# MCP2515_PINOUT.net
KiCad netlist of a schematic drawn in Altium Designer
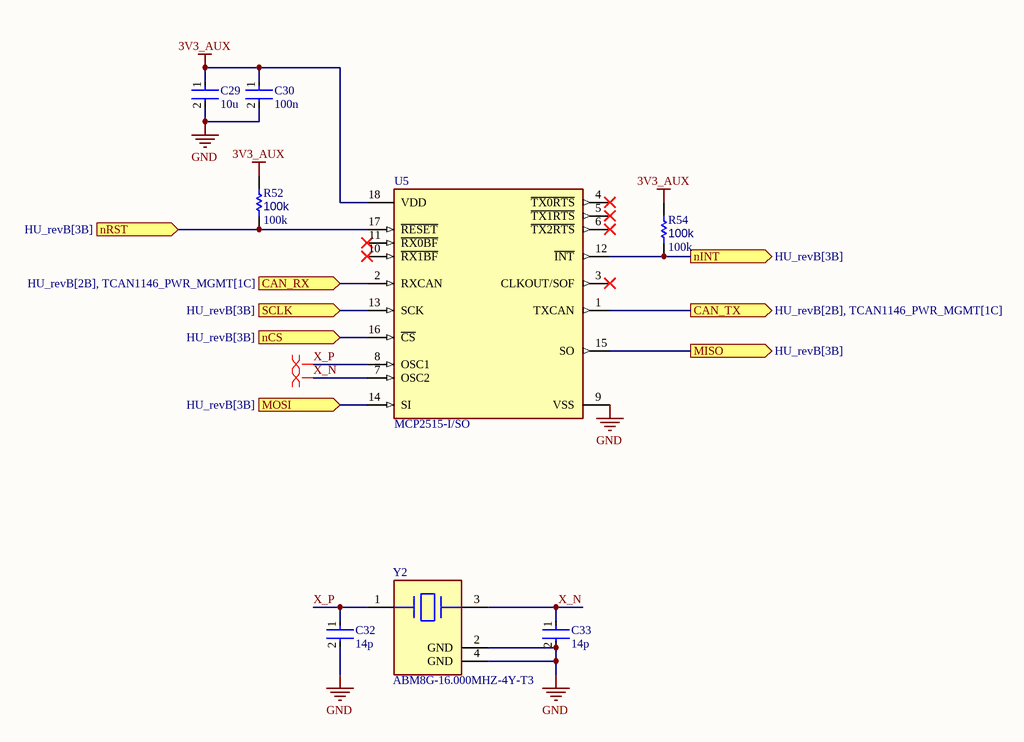
[diagram p0: MCP2515_PINOUT.SchDoc]

(export (version "E")
  (design (tool "Eeschema 10.0.6"))
  (components
    (comp (ref "C29")
      (value "10u")
      (footprint "FP-0402-L_1_0_0_05-W_0_5-IPC_A")
      (description "LARGE PADS, 0402 CAP, CHANGE COMMENT TO MATCH REAL P/N")
      (libsource (lib "Space Concordia") (part "b4654b650e69147ec39a6b967a45e02"))
    )
    (comp (ref "C30")
      (value "100n")
      (footprint "FP-0402-L_1_0_0_05-W_0_5-IPC_A")
      (description "LARGE PADS, 0402 CAP, CHANGE COMMENT TO MATCH REAL P/N")
      (libsource (lib "Space Concordia") (part "b4654b650e69147ec39a6b967a45e02"))
    )
    (comp (ref "C32")
      (value "14p")
      (footprint "FP-0402-L_1_0_0_05-W_0_5-IPC_A")
      (description "LARGE PADS, 0402 CAP, CHANGE COMMENT TO MATCH REAL P/N")
      (libsource (lib "Space Concordia") (part "b4654b650e69147ec39a6b967a45e02"))
    )
    (comp (ref "C33")
      (value "14p")
      (footprint "FP-0402-L_1_0_0_05-W_0_5-IPC_A")
      (description "LARGE PADS, 0402 CAP, CHANGE COMMENT TO MATCH REAL P/N")
      (libsource (lib "Space Concordia") (part "b4654b650e69147ec39a6b967a45e02"))
    )
    (comp (ref "R52")
      (value "100k")
      (footprint "R0603B")
      (description "Resistor")
      (fields (field (name "ALTIUM_VALUE") "100k"))
      (libsource (lib "Space Concordia") (part "Resistor"))
    )
    (comp (ref "R54")
      (value "100k")
      (footprint "R0603B")
      (description "Resistor")
      (fields (field (name "ALTIUM_VALUE") "100k"))
      (libsource (lib "Space Concordia") (part "Resistor"))
    )
    (comp (ref "U5")
      (value "MCP2515-I/SO")
      (footprint "FP-C04-051-MFG")
      (description "IC CAN CONTROLLER W/SPI 18SOIC")
      (fields
        (field (name "MANUFACTURER") "Microchip")
        (field (name "OCTOPART") "https://octopart.com/mcp2515-i%2Fso-microchip-430187")
      )
      (libsource (lib "Altium Content Vault") (part "1c78ea6ff576bac94664e2637e1b479"))
    )
    (comp (ref "Y2")
      (value "ABM8G-16.000MHZ-4Y-T3")
      (footprint "FP-ABM8G-MFG")
      (description "Crystal 16MHz ±30ppm (Tol) ±30ppm (Stability) 10pF FUND 80Ω 4-Pin SMD T/R")
      (libsource (lib "Altium Content Vault") (part "48e526d86b7f2615d98721063c72f49"))
    )
  )
  (nets
    (net (code "1") (name "/CAN_RX") (class "Default")
      (node (ref "U5") (pin "2") (pinfunction "RXCAN_2") (pintype "input"))
    )
    (net (code "2") (name "/CAN_TX") (class "Default")
      (node (ref "U5") (pin "1") (pinfunction "TXCAN_1") (pintype "output"))
    )
    (net (code "3") (name "/MISO") (class "Default")
      (node (ref "U5") (pin "15") (pinfunction "SO_15") (pintype "output"))
    )
    (net (code "4") (name "/MOSI") (class "Default")
      (node (ref "U5") (pin "14") (pinfunction "SI_14") (pintype "input"))
    )
    (net (code "5") (name "/SCLK") (class "Default")
      (node (ref "U5") (pin "13") (pinfunction "SCK_13") (pintype "input"))
    )
    (net (code "6") (name "/X_N") (class "Default")
      (node (ref "C33") (pin "1") (pinfunction "1_1") (pintype "passive"))
      (node (ref "U5") (pin "7") (pinfunction "OSC2_7") (pintype "input"))
      (node (ref "Y2") (pin "3") (pinfunction "3_3") (pintype "passive"))
    )
    (net (code "7") (name "/X_P") (class "Default")
      (node (ref "C32") (pin "1") (pinfunction "1_1") (pintype "passive"))
      (node (ref "U5") (pin "8") (pinfunction "OSC1_8") (pintype "input"))
      (node (ref "Y2") (pin "1") (pinfunction "1_1") (pintype "passive"))
    )
    (net (code "8") (name "/nCS") (class "Default")
      (node (ref "U5") (pin "16") (pinfunction "~{CS}_16") (pintype "input"))
    )
    (net (code "9") (name "/nINT") (class "Default")
      (node (ref "R54") (pin "2") (pinfunction "2_2") (pintype "passive"))
      (node (ref "U5") (pin "12") (pinfunction "~{INT}_12") (pintype "output"))
    )
    (net (code "10") (name "/nRST") (class "Default")
      (node (ref "R52") (pin "2") (pinfunction "2_2") (pintype "passive"))
      (node (ref "U5") (pin "17") (pinfunction "~{RESET}_17") (pintype "input"))
    )
    (net (code "11") (name "3V3_AUX") (class "Default")
      (node (ref "C29") (pin "1") (pinfunction "1_1") (pintype "passive"))
      (node (ref "C30") (pin "1") (pinfunction "1_1") (pintype "passive"))
      (node (ref "R52") (pin "1") (pinfunction "1_1") (pintype "passive"))
      (node (ref "R54") (pin "1") (pinfunction "1_1") (pintype "passive"))
      (node (ref "U5") (pin "18") (pinfunction "VDD_18") (pintype "power_in"))
    )
    (net (code "12") (name "GND") (class "Default")
      (node (ref "C29") (pin "2") (pinfunction "2_2") (pintype "passive"))
      (node (ref "C30") (pin "2") (pinfunction "2_2") (pintype "passive"))
      (node (ref "C32") (pin "2") (pinfunction "2_2") (pintype "passive"))
      (node (ref "C33") (pin "2") (pinfunction "2_2") (pintype "passive"))
      (node (ref "U5") (pin "9") (pinfunction "VSS_9") (pintype "power_in"))
      (node (ref "Y2") (pin "2") (pinfunction "GND_2") (pintype "power_in"))
      (node (ref "Y2") (pin "4") (pinfunction "GND_4") (pintype "power_in"))
    )
    (net (code "13") (name "unconnected-(U5-CLKOUT{slash}SOF-Pad3)") (class "Default")
      (node (ref "U5") (pin "3") (pinfunction "CLKOUT/SOF_3") (pintype "output+no_connect"))
    )
    (net (code "14") (name "unconnected-(U5-~{RX0BF}-Pad11)") (class "Default")
      (node (ref "U5") (pin "11") (pinfunction "~{RX0BF}_11") (pintype "input+no_connect"))
    )
    (net (code "15") (name "unconnected-(U5-~{RX1BF}-Pad10)") (class "Default")
      (node (ref "U5") (pin "10") (pinfunction "~{RX1BF}_10") (pintype "input+no_connect"))
    )
    (net (code "16") (name "unconnected-(U5-~{TX0RTS}-Pad4)") (class "Default")
      (node (ref "U5") (pin "4") (pinfunction "~{TX0RTS}_4") (pintype "output+no_connect"))
    )
    (net (code "17") (name "unconnected-(U5-~{TX1RTS}-Pad5)") (class "Default")
      (node (ref "U5") (pin "5") (pinfunction "~{TX1RTS}_5") (pintype "output+no_connect"))
    )
    (net (code "18") (name "unconnected-(U5-~{TX2RTS}-Pad6)") (class "Default")
      (node (ref "U5") (pin "6") (pinfunction "~{TX2RTS}_6") (pintype "output+no_connect"))
    )
  )
)
